# mainpanel.net
KiCad netlist of a schematic drawn in EAGLE
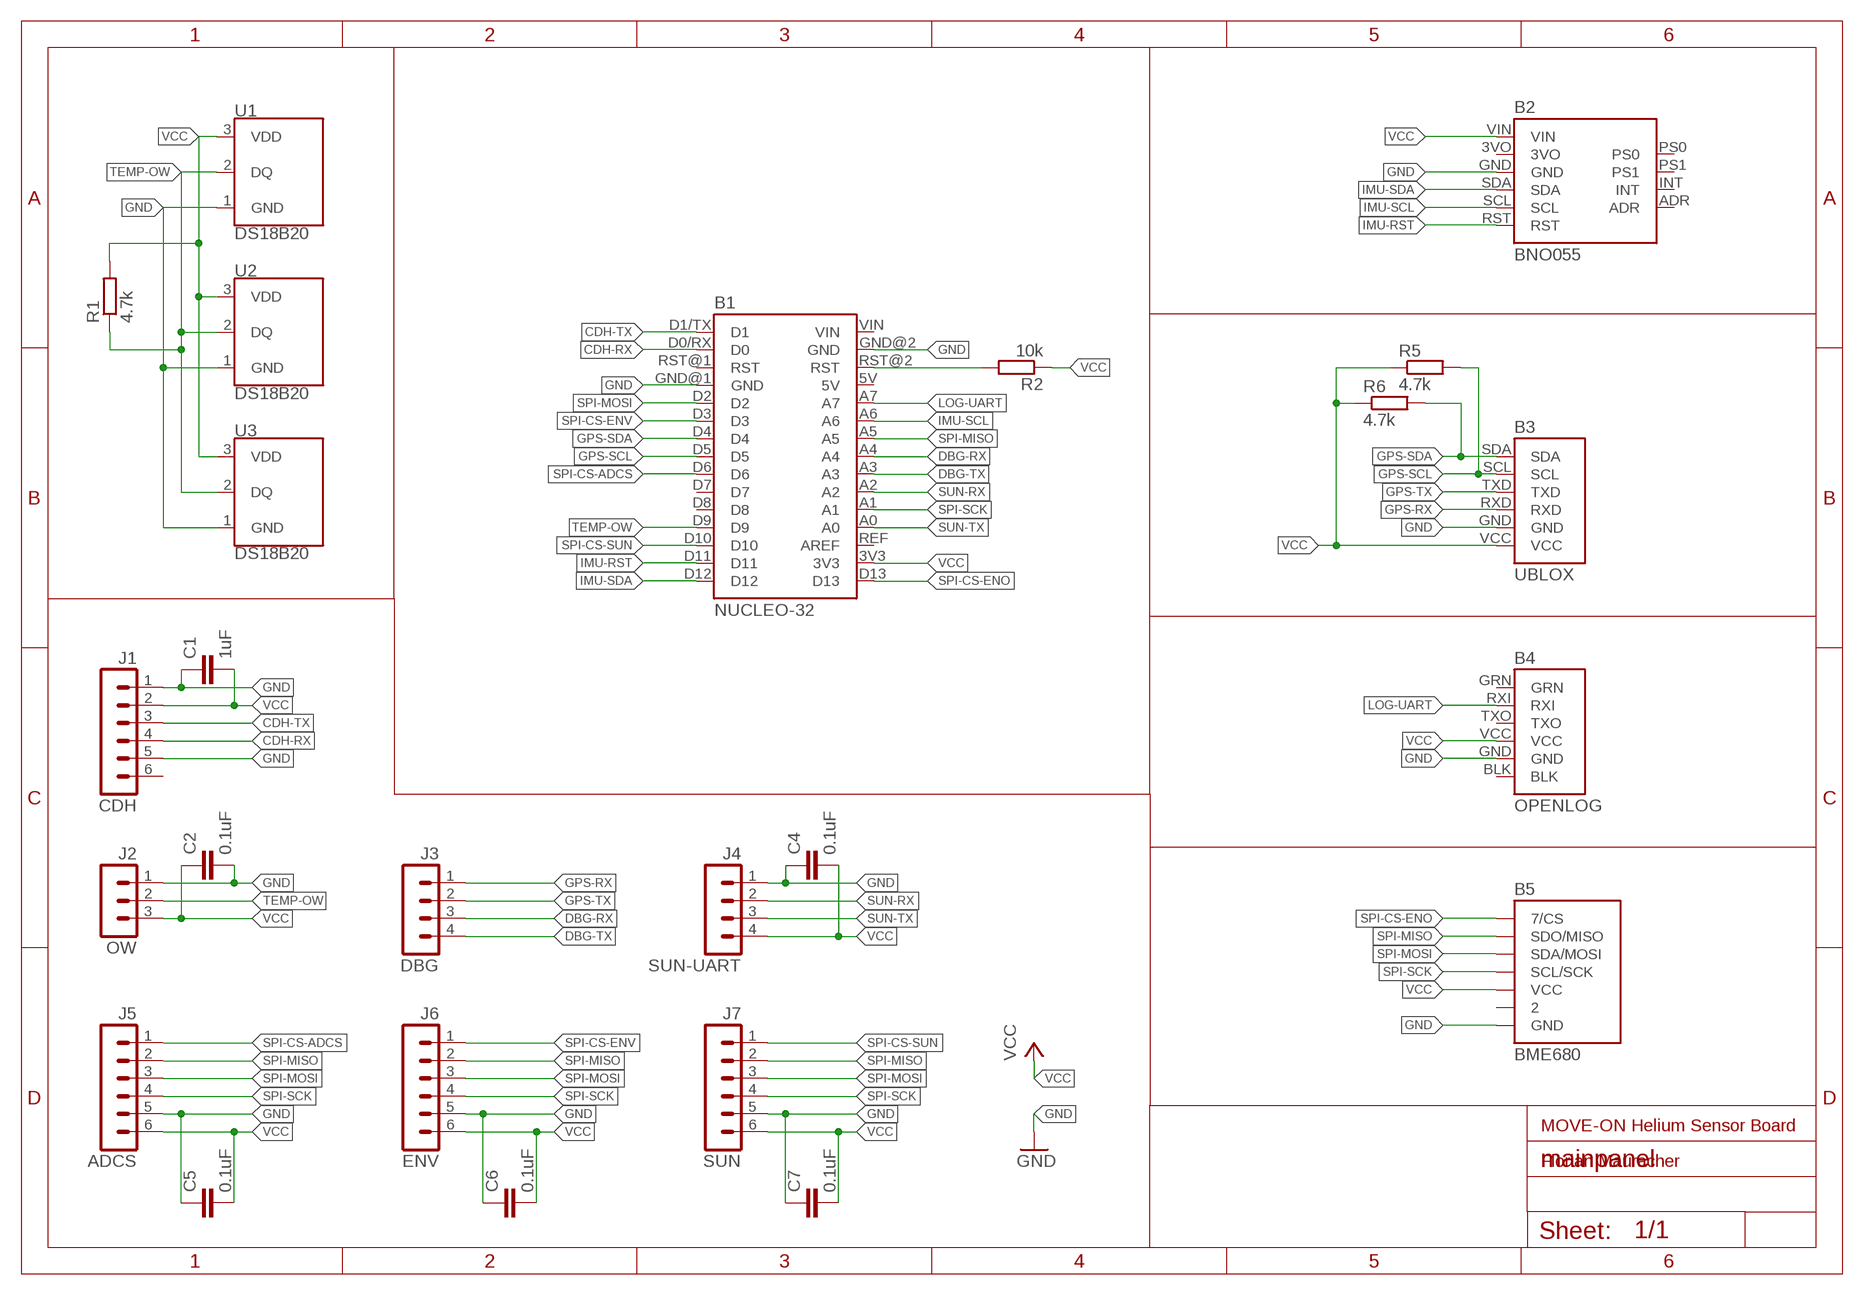
[diagram p0: schematic, sheet 1]

(export (version "E")
  (design (tool "Eeschema 10.0.6"))
  (components
    (comp (ref "B1")
      (value "NUCLEO-32")
      (footprint "eagle-import:NUCLEO-32")
      (libsource (lib "eagle-import") (part "NUCLEO-32BO"))
    )
    (comp (ref "B2")
      (value "BNO055")
      (footprint "eagle-import:BOSCH-BNO055")
      (libsource (lib "eagle-import") (part "BOSCH-BNO055BO"))
    )
    (comp (ref "B3")
      (value "UBLOX")
      (footprint "eagle-import:UPUTRONICS-UBLOX-PICO")
      (libsource (lib "eagle-import") (part "UPUTRONICS-UBLOX-PICOBO"))
    )
    (comp (ref "B4")
      (value "OPENLOG")
      (footprint "eagle-import:SPARKFUN-OPENLOG")
      (libsource (lib "eagle-import") (part "SPARKFUN-OPENLOGBO"))
    )
    (comp (ref "B5")
      (value "BME680")
      (footprint "eagle-import:WATTEROT-BME680")
      (libsource (lib "eagle-import") (part "WATTEROT-BME680BO"))
    )
    (comp (ref "C1")
      (value "1uF")
      (footprint "eagle-import:C2012")
      (libsource (lib "eagle-import") (part "C-EUC2012"))
    )
    (comp (ref "C2")
      (value "0.1uF")
      (footprint "eagle-import:C2012")
      (libsource (lib "eagle-import") (part "C-EUC2012"))
    )
    (comp (ref "C4")
      (value "0.1uF")
      (footprint "eagle-import:C2012")
      (libsource (lib "eagle-import") (part "C-EUC2012"))
    )
    (comp (ref "C5")
      (value "0.1uF")
      (footprint "eagle-import:C2012")
      (libsource (lib "eagle-import") (part "C-EUC2012"))
    )
    (comp (ref "C6")
      (value "0.1uF")
      (footprint "eagle-import:C2012")
      (libsource (lib "eagle-import") (part "C-EUC2012"))
    )
    (comp (ref "C7")
      (value "0.1uF")
      (footprint "eagle-import:C2012")
      (libsource (lib "eagle-import") (part "C-EUC2012"))
    )
    (comp (ref "J1")
      (value "CDH")
      (footprint "eagle-import:90136-1_06")
      (libsource (lib "eagle-import") (part "90136-1?06"))
    )
    (comp (ref "J2")
      (value "OW")
      (footprint "eagle-import:90136-1_03")
      (libsource (lib "eagle-import") (part "90136-1?03"))
    )
    (comp (ref "J3")
      (value "DBG")
      (footprint "eagle-import:90136-1_04")
      (libsource (lib "eagle-import") (part "90136-1?04"))
    )
    (comp (ref "J4")
      (value "SUN-UART")
      (footprint "eagle-import:90136-1_04")
      (libsource (lib "eagle-import") (part "90136-1?04"))
    )
    (comp (ref "J5")
      (value "ADCS")
      (footprint "eagle-import:90136-1_06")
      (libsource (lib "eagle-import") (part "90136-1?06"))
    )
    (comp (ref "J6")
      (value "ENV")
      (footprint "eagle-import:90136-1_06")
      (libsource (lib "eagle-import") (part "90136-1?06"))
    )
    (comp (ref "J7")
      (value "SUN")
      (footprint "eagle-import:90136-1_06")
      (libsource (lib "eagle-import") (part "90136-1?06"))
    )
    (comp (ref "R1")
      (value "4.7k")
      (footprint "eagle-import:R2012")
      (libsource (lib "eagle-import") (part "R-EU_R2012"))
    )
    (comp (ref "R2")
      (value "10k")
      (footprint "eagle-import:R2012")
      (libsource (lib "eagle-import") (part "R-EU_R2012"))
    )
    (comp (ref "R5")
      (value "4.7k")
      (footprint "eagle-import:R2012")
      (libsource (lib "eagle-import") (part "R-EU_R2012"))
    )
    (comp (ref "R6")
      (value "4.7k")
      (footprint "eagle-import:R2012")
      (libsource (lib "eagle-import") (part "R-EU_R2012"))
    )
    (comp (ref "U1")
      (value "DS18B20")
      (footprint "eagle-import:TO-92-AMMO")
      (libsource (lib "eagle-import") (part "DS18B20"))
    )
    (comp (ref "U2")
      (value "DS18B20")
      (footprint "eagle-import:TO-92-AMMO")
      (libsource (lib "eagle-import") (part "DS18B20"))
    )
    (comp (ref "U3")
      (value "DS18B20")
      (footprint "eagle-import:TO-92-AMMO")
      (libsource (lib "eagle-import") (part "DS18B20"))
    )
  )
  (nets
    (net (code "1") (name "/5V") (class "Default")
      (node (ref "B1") (pin "5V") (pinfunction "5V_5V") (pintype "power_in"))
    )
    (net (code "2") (name "/GRN") (class "Default")
      (node (ref "B4") (pin "GRN") (pinfunction "GRN_GRN") (pintype "power_in"))
    )
    (net (code "3") (name "/VIN") (class "Default")
      (node (ref "B1") (pin "VIN") (pinfunction "VIN_VIN") (pintype "power_in"))
    )
    (net (code "4") (name "CDH-RX") (class "Default")
      (node (ref "B1") (pin "D0/RX") (pinfunction "D0_D0/RX") (pintype "bidirectional"))
      (node (ref "J1") (pin "4") (pinfunction "4_4") (pintype "passive"))
    )
    (net (code "5") (name "CDH-TX") (class "Default")
      (node (ref "B1") (pin "D1/TX") (pinfunction "D1_D1/TX") (pintype "bidirectional"))
      (node (ref "J1") (pin "3") (pinfunction "3_3") (pintype "passive"))
    )
    (net (code "6") (name "DBG-RX") (class "Default")
      (node (ref "B1") (pin "A4") (pinfunction "A4_A4") (pintype "bidirectional"))
      (node (ref "J3") (pin "3") (pinfunction "3_3") (pintype "passive"))
    )
    (net (code "7") (name "DBG-TX") (class "Default")
      (node (ref "B1") (pin "A3") (pinfunction "A3_A3") (pintype "bidirectional"))
      (node (ref "J3") (pin "4") (pinfunction "4_4") (pintype "passive"))
    )
    (net (code "8") (name "GND") (class "Default")
      (node (ref "B1") (pin "GND@1") (pinfunction "GND_GND@1") (pintype "power_in"))
      (node (ref "B1") (pin "GND@2") (pinfunction "GND_GND@2") (pintype "power_in"))
      (node (ref "B2") (pin "GND") (pinfunction "GND_GND") (pintype "power_in"))
      (node (ref "B3") (pin "GND") (pinfunction "GND_GND") (pintype "power_in"))
      (node (ref "B4") (pin "GND") (pinfunction "GND_GND") (pintype "power_in"))
      (node (ref "B5") (pin "GND") (pinfunction "GND_GND") (pintype "power_in"))
      (node (ref "C1") (pin "1") (pinfunction "1_1") (pintype "passive"))
      (node (ref "C2") (pin "2") (pinfunction "2_2") (pintype "passive"))
      (node (ref "C4") (pin "1") (pinfunction "1_1") (pintype "passive"))
      (node (ref "C5") (pin "1") (pinfunction "1_1") (pintype "passive"))
      (node (ref "C6") (pin "1") (pinfunction "1_1") (pintype "passive"))
      (node (ref "C7") (pin "1") (pinfunction "1_1") (pintype "passive"))
      (node (ref "J1") (pin "1") (pinfunction "1_1") (pintype "passive"))
      (node (ref "J1") (pin "5") (pinfunction "5_5") (pintype "passive"))
      (node (ref "J2") (pin "1") (pinfunction "1_1") (pintype "passive"))
      (node (ref "J4") (pin "1") (pinfunction "1_1") (pintype "passive"))
      (node (ref "J5") (pin "5") (pinfunction "5_5") (pintype "passive"))
      (node (ref "J6") (pin "5") (pinfunction "5_5") (pintype "passive"))
      (node (ref "J7") (pin "5") (pinfunction "5_5") (pintype "passive"))
      (node (ref "U1") (pin "1") (pinfunction "GND_1") (pintype "power_in"))
      (node (ref "U2") (pin "1") (pinfunction "GND_1") (pintype "power_in"))
      (node (ref "U3") (pin "1") (pinfunction "GND_1") (pintype "power_in"))
    )
    (net (code "9") (name "GPS-RX") (class "Default")
      (node (ref "B3") (pin "RXD") (pinfunction "RXD_RXD") (pintype "bidirectional"))
      (node (ref "J3") (pin "1") (pinfunction "1_1") (pintype "passive"))
    )
    (net (code "10") (name "GPS-SCL") (class "Default")
      (node (ref "B1") (pin "D5") (pinfunction "D5_D5") (pintype "bidirectional"))
      (node (ref "B3") (pin "SCL") (pinfunction "SCL_SCL") (pintype "bidirectional"))
      (node (ref "R5") (pin "2") (pinfunction "2_2") (pintype "passive"))
    )
    (net (code "11") (name "GPS-SDA") (class "Default")
      (node (ref "B1") (pin "D4") (pinfunction "D4_D4") (pintype "bidirectional"))
      (node (ref "B3") (pin "SDA") (pinfunction "SDA_SDA") (pintype "bidirectional"))
      (node (ref "R6") (pin "2") (pinfunction "2_2") (pintype "passive"))
    )
    (net (code "12") (name "GPS-TX") (class "Default")
      (node (ref "B3") (pin "TXD") (pinfunction "TXD_TXD") (pintype "bidirectional"))
      (node (ref "J3") (pin "2") (pinfunction "2_2") (pintype "passive"))
    )
    (net (code "13") (name "IMU-RST") (class "Default")
      (node (ref "B1") (pin "D11") (pinfunction "D11_D11") (pintype "bidirectional"))
      (node (ref "B2") (pin "RST") (pinfunction "RST_RST") (pintype "bidirectional"))
    )
    (net (code "14") (name "IMU-SCL") (class "Default")
      (node (ref "B1") (pin "A6") (pinfunction "A6_A6") (pintype "bidirectional"))
      (node (ref "B2") (pin "SCL") (pinfunction "SCL_SCL") (pintype "bidirectional"))
    )
    (net (code "15") (name "IMU-SDA") (class "Default")
      (node (ref "B1") (pin "D12") (pinfunction "D12_D12") (pintype "bidirectional"))
      (node (ref "B2") (pin "SDA") (pinfunction "SDA_SDA") (pintype "bidirectional"))
    )
    (net (code "16") (name "LOG-UART") (class "Default")
      (node (ref "B1") (pin "A7") (pinfunction "A7_A7") (pintype "bidirectional"))
      (node (ref "B4") (pin "RXI") (pinfunction "RXI_RXI") (pintype "input"))
    )
    (net (code "17") (name "Net-(B1-RST-PadRST@2)") (class "Default")
      (node (ref "B1") (pin "RST@2") (pinfunction "RST_RST@2") (pintype "bidirectional"))
      (node (ref "R2") (pin "2") (pinfunction "2_2") (pintype "passive"))
    )
    (net (code "18") (name "SPI-CS-ADCS") (class "Default")
      (node (ref "B1") (pin "D6") (pinfunction "D6_D6") (pintype "bidirectional"))
      (node (ref "J5") (pin "1") (pinfunction "1_1") (pintype "passive"))
    )
    (net (code "19") (name "SPI-CS-ENO") (class "Default")
      (node (ref "B1") (pin "D13") (pinfunction "D13_D13") (pintype "bidirectional"))
      (node (ref "B5") (pin "CS") (pinfunction "7/CS_CS") (pintype "input"))
    )
    (net (code "20") (name "SPI-CS-ENV") (class "Default")
      (node (ref "B1") (pin "D3") (pinfunction "D3_D3") (pintype "bidirectional"))
      (node (ref "J6") (pin "1") (pinfunction "1_1") (pintype "passive"))
    )
    (net (code "21") (name "SPI-CS-SUN") (class "Default")
      (node (ref "B1") (pin "D10") (pinfunction "D10_D10") (pintype "bidirectional"))
      (node (ref "J7") (pin "1") (pinfunction "1_1") (pintype "passive"))
    )
    (net (code "22") (name "SPI-MISO") (class "Default")
      (node (ref "B1") (pin "A5") (pinfunction "A5_A5") (pintype "bidirectional"))
      (node (ref "B5") (pin "SDO/MISO") (pinfunction "SDO/MISO_SDO/MISO") (pintype "output"))
      (node (ref "J5") (pin "2") (pinfunction "2_2") (pintype "passive"))
      (node (ref "J6") (pin "2") (pinfunction "2_2") (pintype "passive"))
      (node (ref "J7") (pin "2") (pinfunction "2_2") (pintype "passive"))
    )
    (net (code "23") (name "SPI-MOSI") (class "Default")
      (node (ref "B1") (pin "D2") (pinfunction "D2_D2") (pintype "bidirectional"))
      (node (ref "B5") (pin "SDA/MOSI") (pinfunction "SDA/MOSI_SDA/MOSI") (pintype "input"))
      (node (ref "J5") (pin "3") (pinfunction "3_3") (pintype "passive"))
      (node (ref "J6") (pin "3") (pinfunction "3_3") (pintype "passive"))
      (node (ref "J7") (pin "3") (pinfunction "3_3") (pintype "passive"))
    )
    (net (code "24") (name "SPI-SCK") (class "Default")
      (node (ref "B1") (pin "A1") (pinfunction "A1_A1") (pintype "bidirectional"))
      (node (ref "B5") (pin "SCL/SCK") (pinfunction "SCL/SCK_SCL/SCK") (pintype "input"))
      (node (ref "J5") (pin "4") (pinfunction "4_4") (pintype "passive"))
      (node (ref "J6") (pin "4") (pinfunction "4_4") (pintype "passive"))
      (node (ref "J7") (pin "4") (pinfunction "4_4") (pintype "passive"))
    )
    (net (code "25") (name "SUN-RX") (class "Default")
      (node (ref "B1") (pin "A2") (pinfunction "A2_A2") (pintype "bidirectional"))
      (node (ref "J4") (pin "2") (pinfunction "2_2") (pintype "passive"))
    )
    (net (code "26") (name "SUN-TX") (class "Default")
      (node (ref "B1") (pin "A0") (pinfunction "A0_A0") (pintype "bidirectional"))
      (node (ref "J4") (pin "3") (pinfunction "3_3") (pintype "passive"))
    )
    (net (code "27") (name "TEMP-OW") (class "Default")
      (node (ref "B1") (pin "D9") (pinfunction "D9_D9") (pintype "bidirectional"))
      (node (ref "J2") (pin "2") (pinfunction "2_2") (pintype "passive"))
      (node (ref "R1") (pin "1") (pinfunction "1_1") (pintype "passive"))
      (node (ref "U1") (pin "2") (pinfunction "DQ_2") (pintype "bidirectional"))
      (node (ref "U2") (pin "2") (pinfunction "DQ_2") (pintype "bidirectional"))
      (node (ref "U3") (pin "2") (pinfunction "DQ_2") (pintype "bidirectional"))
    )
    (net (code "28") (name "VCC") (class "Default")
      (node (ref "B1") (pin "3V3") (pinfunction "3V3_3V3") (pintype "power_in"))
      (node (ref "B2") (pin "VIN") (pinfunction "VIN_VIN") (pintype "power_in"))
      (node (ref "B3") (pin "VCC") (pinfunction "VCC_VCC") (pintype "power_in"))
      (node (ref "B4") (pin "VCC") (pinfunction "VCC_VCC") (pintype "power_in"))
      (node (ref "B5") (pin "VCC") (pinfunction "VCC_VCC") (pintype "power_in"))
      (node (ref "C1") (pin "2") (pinfunction "2_2") (pintype "passive"))
      (node (ref "C2") (pin "1") (pinfunction "1_1") (pintype "passive"))
      (node (ref "C4") (pin "2") (pinfunction "2_2") (pintype "passive"))
      (node (ref "C5") (pin "2") (pinfunction "2_2") (pintype "passive"))
      (node (ref "C6") (pin "2") (pinfunction "2_2") (pintype "passive"))
      (node (ref "C7") (pin "2") (pinfunction "2_2") (pintype "passive"))
      (node (ref "J1") (pin "2") (pinfunction "2_2") (pintype "passive"))
      (node (ref "J2") (pin "3") (pinfunction "3_3") (pintype "passive"))
      (node (ref "J4") (pin "4") (pinfunction "4_4") (pintype "passive"))
      (node (ref "J5") (pin "6") (pinfunction "6_6") (pintype "passive"))
      (node (ref "J6") (pin "6") (pinfunction "6_6") (pintype "passive"))
      (node (ref "J7") (pin "6") (pinfunction "6_6") (pintype "passive"))
      (node (ref "R1") (pin "2") (pinfunction "2_2") (pintype "passive"))
      (node (ref "R2") (pin "1") (pinfunction "1_1") (pintype "passive"))
      (node (ref "R5") (pin "1") (pinfunction "1_1") (pintype "passive"))
      (node (ref "R6") (pin "1") (pinfunction "1_1") (pintype "passive"))
      (node (ref "U1") (pin "3") (pinfunction "VDD_3") (pintype "power_in"))
      (node (ref "U2") (pin "3") (pinfunction "VDD_3") (pintype "power_in"))
      (node (ref "U3") (pin "3") (pinfunction "VDD_3") (pintype "power_in"))
    )
    (net (code "29") (name "unconnected-(B1-AREF-PadREF)") (class "Default")
      (node (ref "B1") (pin "REF") (pinfunction "AREF_REF") (pintype "bidirectional"))
    )
    (net (code "30") (name "unconnected-(B1-PadD7)") (class "Default")
      (node (ref "B1") (pin "D7") (pinfunction "D7_D7") (pintype "bidirectional"))
    )
    (net (code "31") (name "unconnected-(B1-PadD8)") (class "Default")
      (node (ref "B1") (pin "D8") (pinfunction "D8_D8") (pintype "bidirectional"))
    )
    (net (code "32") (name "unconnected-(B1-RST-PadRST@1)") (class "Default")
      (node (ref "B1") (pin "RST@1") (pinfunction "RST_RST@1") (pintype "bidirectional"))
    )
    (net (code "33") (name "unconnected-(B2-Pad3VO)") (class "Default")
      (node (ref "B2") (pin "3VO") (pinfunction "3VO_3VO") (pintype "bidirectional"))
    )
    (net (code "34") (name "unconnected-(B2-PadADR)") (class "Default")
      (node (ref "B2") (pin "ADR") (pinfunction "ADR_ADR") (pintype "bidirectional"))
    )
    (net (code "35") (name "unconnected-(B2-PadINT)") (class "Default")
      (node (ref "B2") (pin "INT") (pinfunction "INT_INT") (pintype "bidirectional"))
    )
    (net (code "36") (name "unconnected-(B2-PadPS0)") (class "Default")
      (node (ref "B2") (pin "PS0") (pinfunction "PS0_PS0") (pintype "bidirectional"))
    )
    (net (code "37") (name "unconnected-(B2-PadPS1)") (class "Default")
      (node (ref "B2") (pin "PS1") (pinfunction "PS1_PS1") (pintype "bidirectional"))
    )
    (net (code "38") (name "unconnected-(B4-PadBLK)") (class "Default")
      (node (ref "B4") (pin "BLK") (pinfunction "BLK_BLK") (pintype "bidirectional"))
    )
    (net (code "39") (name "unconnected-(B4-PadTXO)") (class "Default")
      (node (ref "B4") (pin "TXO") (pinfunction "TXO_TXO") (pintype "output"))
    )
    (net (code "40") (name "unconnected-(B5-Pad2)") (class "Default")
      (node (ref "B5") (pin "2") (pinfunction "2_2") (pintype "no_connect"))
    )
    (net (code "41") (name "unconnected-(J1-Pad6)") (class "Default")
      (node (ref "J1") (pin "6") (pinfunction "6_6") (pintype "passive"))
    )
  )
)
